# HP32W_grove.net
KiCad netlist of a schematic drawn in EAGLE
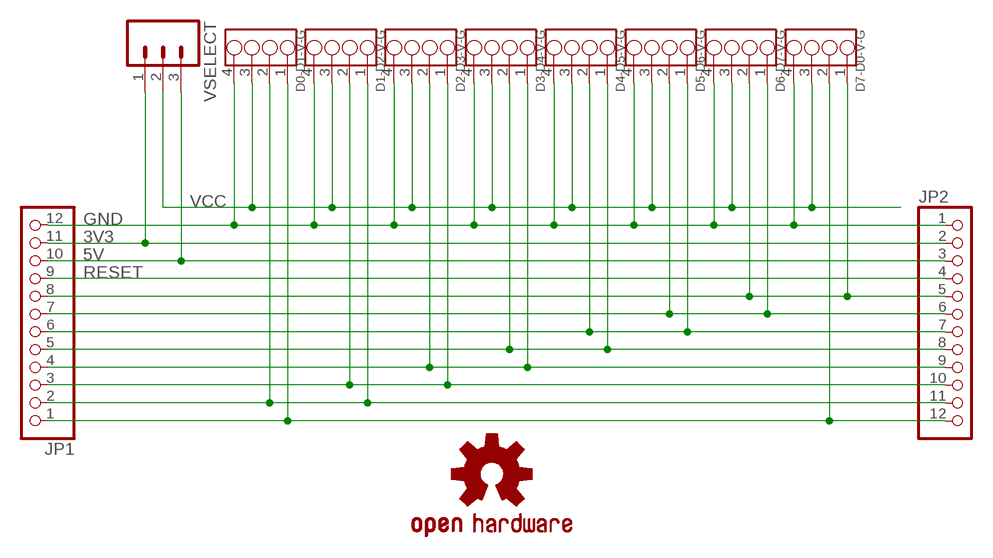
[diagram p0: schematic, sheet 1]

(export (version "E")
  (design (tool "Eeschema 10.0.6"))
  (components
    (comp (ref "D0-D1-V-G")
      (value "GROVE-4P-2.0-3470130P1")
      (footprint "eagle-import:4P-2.0")
      (libsource (lib "eagle-import") (part "GROVE-4P-2.0-3470130P1"))
    )
    (comp (ref "D1-D2-V-G")
      (value "GROVE-4P-2.0-3470130P1")
      (footprint "eagle-import:4P-2.0")
      (libsource (lib "eagle-import") (part "GROVE-4P-2.0-3470130P1"))
    )
    (comp (ref "D2-D3-V-G")
      (value "GROVE-4P-2.0-3470130P1")
      (footprint "eagle-import:4P-2.0")
      (libsource (lib "eagle-import") (part "GROVE-4P-2.0-3470130P1"))
    )
    (comp (ref "D3-D4-V-G")
      (value "GROVE-4P-2.0-3470130P1")
      (footprint "eagle-import:4P-2.0")
      (libsource (lib "eagle-import") (part "GROVE-4P-2.0-3470130P1"))
    )
    (comp (ref "D4-D5-V-G")
      (value "GROVE-4P-2.0-3470130P1")
      (footprint "eagle-import:4P-2.0")
      (libsource (lib "eagle-import") (part "GROVE-4P-2.0-3470130P1"))
    )
    (comp (ref "D5-D6-V-G")
      (value "GROVE-4P-2.0-3470130P1")
      (footprint "eagle-import:4P-2.0")
      (libsource (lib "eagle-import") (part "GROVE-4P-2.0-3470130P1"))
    )
    (comp (ref "D6-D7-V-G")
      (value "GROVE-4P-2.0-3470130P1")
      (footprint "eagle-import:4P-2.0")
      (libsource (lib "eagle-import") (part "GROVE-4P-2.0-3470130P1"))
    )
    (comp (ref "D7-D0-V-G")
      (value "GROVE-4P-2.0-3470130P1")
      (footprint "eagle-import:4P-2.0")
      (libsource (lib "eagle-import") (part "GROVE-4P-2.0-3470130P1"))
    )
    (comp (ref "JP1")
      (value "PINHD-1X12-CB")
      (footprint "eagle-import:1X12-CB")
      (libsource (lib "eagle-import") (part "PINHD-1X12-CB"))
    )
    (comp (ref "JP2")
      (value "PINHD-1X12-CB")
      (footprint "eagle-import:1X12-CB")
      (libsource (lib "eagle-import") (part "PINHD-1X12-CB"))
    )
    (comp (ref "LOGO1")
      (value "OSHW-LOGOS")
      (footprint "eagle-import:OSHW-LOGO-S")
      (libsource (lib "eagle-import") (part "OSHW-LOGOS"))
    )
    (comp (ref "VSELECT")
      (value "M03PTH")
      (footprint "eagle-import:1X03")
      (libsource (lib "eagle-import") (part "M03PTH"))
    )
  )
  (nets
    (net (code "1") (name "/3V3") (class "Default")
      (node (ref "JP1") (pin "11") (pinfunction "11_11") (pintype "passive"))
      (node (ref "JP2") (pin "2") (pinfunction "2_2") (pintype "passive"))
      (node (ref "VSELECT") (pin "1") (pinfunction "1_1") (pintype "passive"))
    )
    (net (code "2") (name "/5V") (class "Default")
      (node (ref "JP1") (pin "10") (pinfunction "10_10") (pintype "passive"))
      (node (ref "JP2") (pin "3") (pinfunction "3_3") (pintype "passive"))
      (node (ref "VSELECT") (pin "3") (pinfunction "3_3") (pintype "passive"))
    )
    (net (code "3") (name "/GND") (class "Default")
      (node (ref "D0-D1-V-G") (pin "4") (pinfunction "4_4") (pintype "bidirectional"))
      (node (ref "D1-D2-V-G") (pin "4") (pinfunction "4_4") (pintype "bidirectional"))
      (node (ref "D2-D3-V-G") (pin "4") (pinfunction "4_4") (pintype "bidirectional"))
      (node (ref "D3-D4-V-G") (pin "4") (pinfunction "4_4") (pintype "bidirectional"))
      (node (ref "D4-D5-V-G") (pin "4") (pinfunction "4_4") (pintype "bidirectional"))
      (node (ref "D5-D6-V-G") (pin "4") (pinfunction "4_4") (pintype "bidirectional"))
      (node (ref "D6-D7-V-G") (pin "4") (pinfunction "4_4") (pintype "bidirectional"))
      (node (ref "D7-D0-V-G") (pin "4") (pinfunction "4_4") (pintype "bidirectional"))
      (node (ref "JP1") (pin "12") (pinfunction "12_12") (pintype "passive"))
      (node (ref "JP2") (pin "1") (pinfunction "1_1") (pintype "passive"))
    )
    (net (code "4") (name "/RESET") (class "Default")
      (node (ref "JP1") (pin "9") (pinfunction "9_9") (pintype "passive"))
      (node (ref "JP2") (pin "4") (pinfunction "4_4") (pintype "passive"))
    )
    (net (code "5") (name "/VCC") (class "Default")
      (node (ref "D0-D1-V-G") (pin "3") (pinfunction "3_3") (pintype "bidirectional"))
      (node (ref "D1-D2-V-G") (pin "3") (pinfunction "3_3") (pintype "bidirectional"))
      (node (ref "D2-D3-V-G") (pin "3") (pinfunction "3_3") (pintype "bidirectional"))
      (node (ref "D3-D4-V-G") (pin "3") (pinfunction "3_3") (pintype "bidirectional"))
      (node (ref "D4-D5-V-G") (pin "3") (pinfunction "3_3") (pintype "bidirectional"))
      (node (ref "D5-D6-V-G") (pin "3") (pinfunction "3_3") (pintype "bidirectional"))
      (node (ref "D6-D7-V-G") (pin "3") (pinfunction "3_3") (pintype "bidirectional"))
      (node (ref "D7-D0-V-G") (pin "3") (pinfunction "3_3") (pintype "bidirectional"))
      (node (ref "VSELECT") (pin "2") (pinfunction "2_2") (pintype "passive"))
    )
    (net (code "6") (name "Net-(D0-D1-V-G-Pad1)") (class "Default")
      (node (ref "D0-D1-V-G") (pin "1") (pinfunction "1_1") (pintype "bidirectional"))
      (node (ref "D7-D0-V-G") (pin "2") (pinfunction "2_2") (pintype "bidirectional"))
      (node (ref "JP1") (pin "1") (pinfunction "1_1") (pintype "passive"))
      (node (ref "JP2") (pin "12") (pinfunction "12_12") (pintype "passive"))
    )
    (net (code "7") (name "Net-(D0-D1-V-G-Pad2)") (class "Default")
      (node (ref "D0-D1-V-G") (pin "2") (pinfunction "2_2") (pintype "bidirectional"))
      (node (ref "D1-D2-V-G") (pin "1") (pinfunction "1_1") (pintype "bidirectional"))
      (node (ref "JP1") (pin "2") (pinfunction "2_2") (pintype "passive"))
      (node (ref "JP2") (pin "11") (pinfunction "11_11") (pintype "passive"))
    )
    (net (code "8") (name "Net-(D1-D2-V-G-Pad2)") (class "Default")
      (node (ref "D1-D2-V-G") (pin "2") (pinfunction "2_2") (pintype "bidirectional"))
      (node (ref "D2-D3-V-G") (pin "1") (pinfunction "1_1") (pintype "bidirectional"))
      (node (ref "JP1") (pin "3") (pinfunction "3_3") (pintype "passive"))
      (node (ref "JP2") (pin "10") (pinfunction "10_10") (pintype "passive"))
    )
    (net (code "9") (name "Net-(D2-D3-V-G-Pad2)") (class "Default")
      (node (ref "D2-D3-V-G") (pin "2") (pinfunction "2_2") (pintype "bidirectional"))
      (node (ref "D3-D4-V-G") (pin "1") (pinfunction "1_1") (pintype "bidirectional"))
      (node (ref "JP1") (pin "4") (pinfunction "4_4") (pintype "passive"))
      (node (ref "JP2") (pin "9") (pinfunction "9_9") (pintype "passive"))
    )
    (net (code "10") (name "Net-(D3-D4-V-G-Pad2)") (class "Default")
      (node (ref "D3-D4-V-G") (pin "2") (pinfunction "2_2") (pintype "bidirectional"))
      (node (ref "D4-D5-V-G") (pin "1") (pinfunction "1_1") (pintype "bidirectional"))
      (node (ref "JP1") (pin "5") (pinfunction "5_5") (pintype "passive"))
      (node (ref "JP2") (pin "8") (pinfunction "8_8") (pintype "passive"))
    )
    (net (code "11") (name "Net-(D4-D5-V-G-Pad2)") (class "Default")
      (node (ref "D4-D5-V-G") (pin "2") (pinfunction "2_2") (pintype "bidirectional"))
      (node (ref "D5-D6-V-G") (pin "1") (pinfunction "1_1") (pintype "bidirectional"))
      (node (ref "JP1") (pin "6") (pinfunction "6_6") (pintype "passive"))
      (node (ref "JP2") (pin "7") (pinfunction "7_7") (pintype "passive"))
    )
    (net (code "12") (name "Net-(D5-D6-V-G-Pad2)") (class "Default")
      (node (ref "D5-D6-V-G") (pin "2") (pinfunction "2_2") (pintype "bidirectional"))
      (node (ref "D6-D7-V-G") (pin "1") (pinfunction "1_1") (pintype "bidirectional"))
      (node (ref "JP1") (pin "7") (pinfunction "7_7") (pintype "passive"))
      (node (ref "JP2") (pin "6") (pinfunction "6_6") (pintype "passive"))
    )
    (net (code "13") (name "Net-(D6-D7-V-G-Pad2)") (class "Default")
      (node (ref "D6-D7-V-G") (pin "2") (pinfunction "2_2") (pintype "bidirectional"))
      (node (ref "D7-D0-V-G") (pin "1") (pinfunction "1_1") (pintype "bidirectional"))
      (node (ref "JP1") (pin "8") (pinfunction "8_8") (pintype "passive"))
      (node (ref "JP2") (pin "5") (pinfunction "5_5") (pintype "passive"))
    )
  )
)
